# PennyMan_Ard_R3_Shield_v9_4.net
KiCad netlist of a schematic drawn in EAGLE
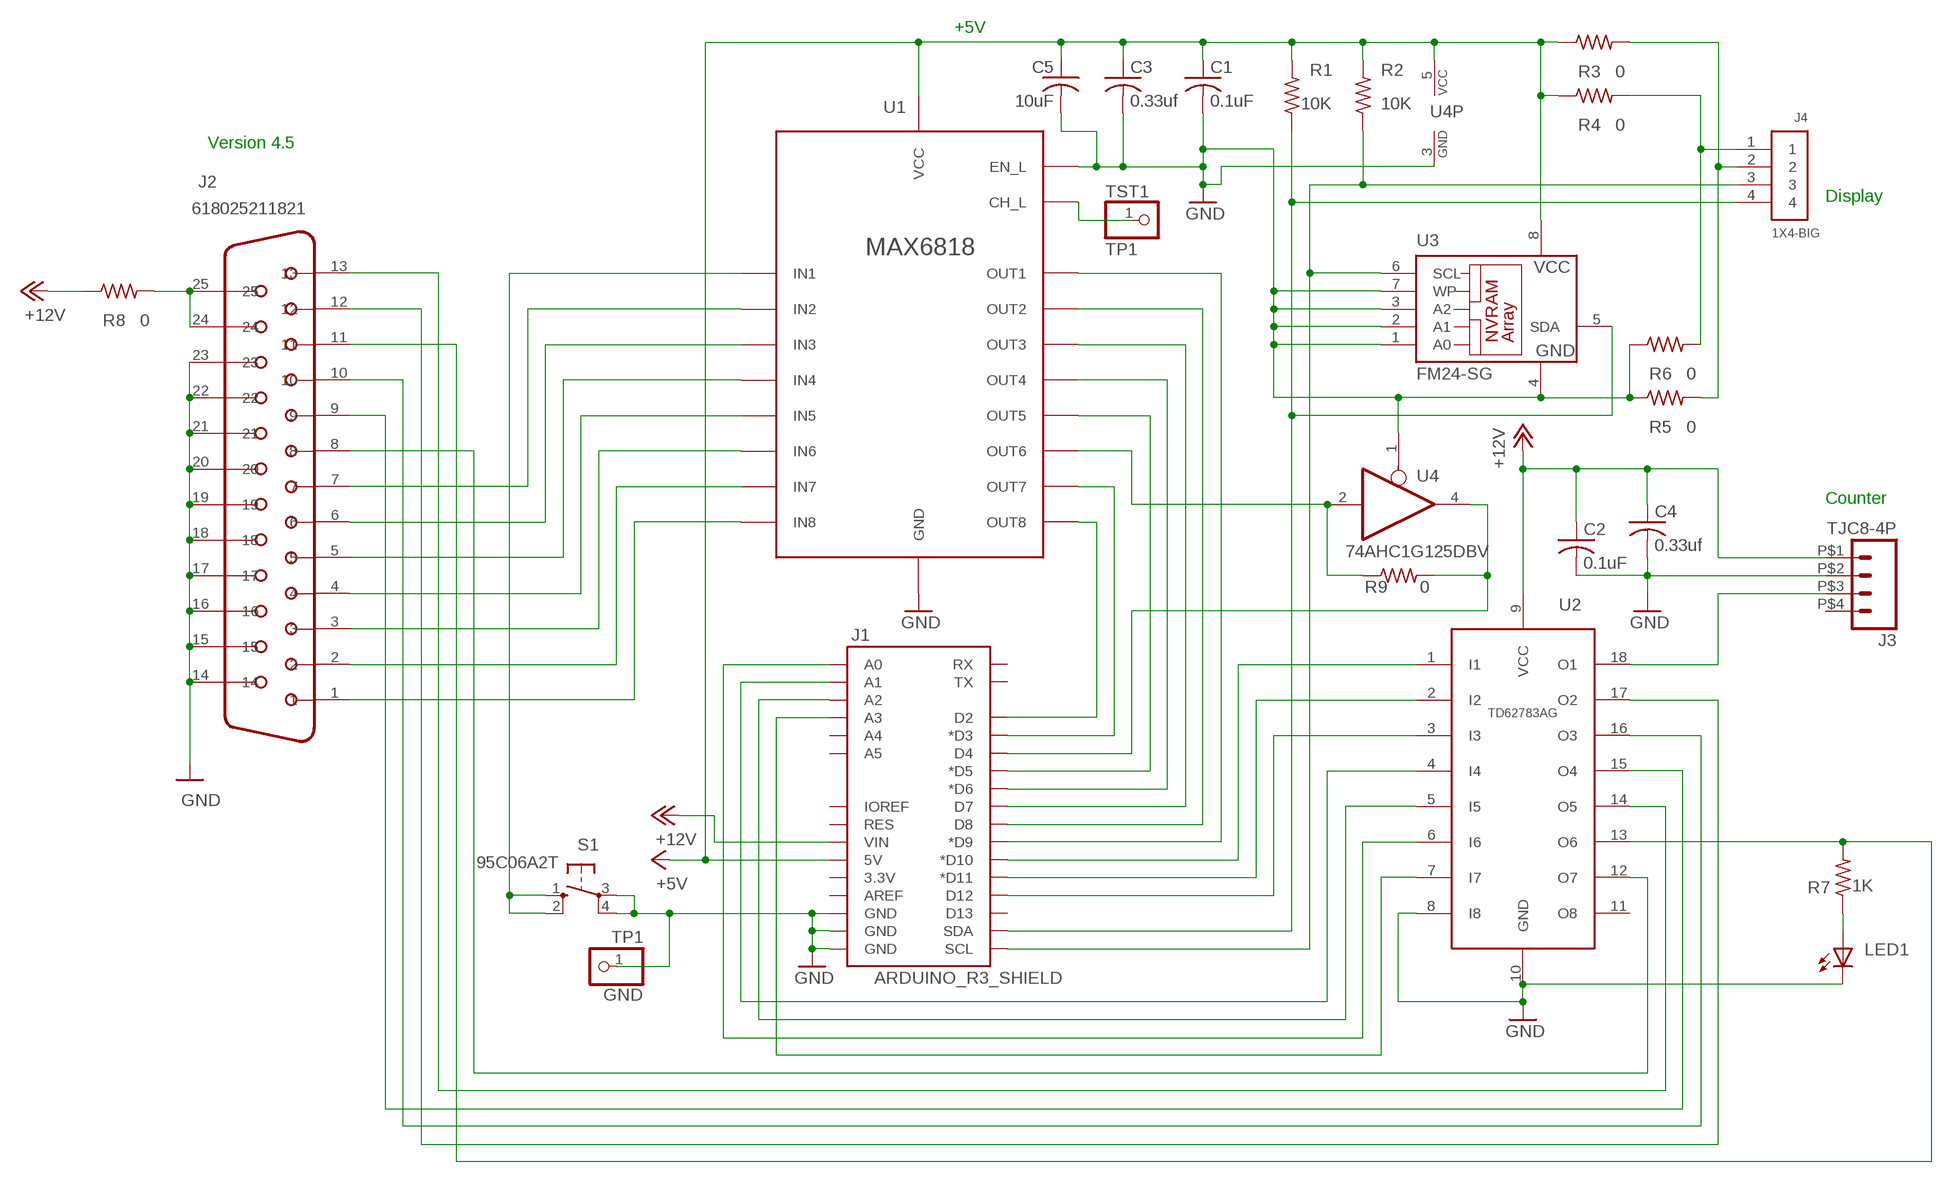
[diagram p0: schematic, sheet 1]

(export (version "E")
  (design (tool "Eeschema 10.0.6"))
  (components
    (comp (ref "C1")
      (value "0.1uF")
      (footprint "eagle-import:C0805")
      (libsource (lib "eagle-import") (part "C-USC0805"))
    )
    (comp (ref "C2")
      (value "0.1uF")
      (footprint "eagle-import:C0805")
      (libsource (lib "eagle-import") (part "C-USC0805"))
    )
    (comp (ref "C3")
      (value "0.33uf")
      (footprint "eagle-import:C1206")
      (libsource (lib "eagle-import") (part "C-USC1206"))
    )
    (comp (ref "C4")
      (value "0.33uf")
      (footprint "eagle-import:C1206")
      (libsource (lib "eagle-import") (part "C-USC1206"))
    )
    (comp (ref "C5")
      (value "10uF")
      (footprint "eagle-import:C1812")
      (libsource (lib "eagle-import") (part "C-USC1812"))
    )
    (comp (ref "GND")
      (value "TP1")
      (footprint "eagle-import:1X01")
      (libsource (lib "eagle-import") (part "PINHD-1X1"))
    )
    (comp (ref "J1")
      (value "ARDUINO_R3_SHIELD")
      (footprint "eagle-import:UNO_R3_SHIELD")
      (libsource (lib "eagle-import") (part "ARDUINO_R3_SHIELD"))
    )
    (comp (ref "J2")
      (value "618025211821")
      (footprint "eagle-import:618025211821")
      (libsource (lib "eagle-import") (part "618025211821"))
    )
    (comp (ref "J3")
      (value "TJC8-4P")
      (footprint "eagle-import:TJC8-4P")
      (libsource (lib "eagle-import") (part "TJC8-4P"))
    )
    (comp (ref "J4")
      (value "1X4-BIG")
      (footprint "eagle-import:1X04-BIG")
      (libsource (lib "eagle-import") (part "1X4-BIG"))
    )
    (comp (ref "LED1")
      (value "LEDSML0805")
      (footprint "eagle-import:SML0805")
      (libsource (lib "eagle-import") (part "LEDSML0805"))
    )
    (comp (ref "R1")
      (value "10K")
      (footprint "eagle-import:R0805")
      (libsource (lib "eagle-import") (part "R-US_R0805"))
    )
    (comp (ref "R2")
      (value "10K")
      (footprint "eagle-import:R0805")
      (libsource (lib "eagle-import") (part "R-US_R0805"))
    )
    (comp (ref "R3")
      (value "0")
      (footprint "eagle-import:R0805")
      (libsource (lib "eagle-import") (part "R-US_R0805"))
    )
    (comp (ref "R4")
      (value "0")
      (footprint "eagle-import:R0805")
      (libsource (lib "eagle-import") (part "R-US_R0805"))
    )
    (comp (ref "R5")
      (value "0")
      (footprint "eagle-import:R0805")
      (libsource (lib "eagle-import") (part "R-US_R0805"))
    )
    (comp (ref "R6")
      (value "0")
      (footprint "eagle-import:R0805")
      (libsource (lib "eagle-import") (part "R-US_R0805"))
    )
    (comp (ref "R7")
      (value "1K")
      (footprint "eagle-import:R0805")
      (libsource (lib "eagle-import") (part "R-US_R0805"))
    )
    (comp (ref "R8")
      (value "0")
      (footprint "eagle-import:R0805")
      (libsource (lib "eagle-import") (part "R-US_R0805"))
    )
    (comp (ref "R9")
      (value "0")
      (footprint "eagle-import:R0805")
      (libsource (lib "eagle-import") (part "R-US_R0805"))
    )
    (comp (ref "S1")
      (value "95C06A2T")
      (footprint "eagle-import:B3F-10XX")
      (libsource (lib "eagle-import") (part "10-XX"))
    )
    (comp (ref "TST1")
      (value "TP1")
      (footprint "eagle-import:1X01")
      (libsource (lib "eagle-import") (part "PINHD-1X1"))
    )
    (comp (ref "U1")
      (value "MAX6818")
      (footprint "eagle-import:SSOP20")
      (libsource (lib "eagle-import") (part "MAX6818"))
    )
    (comp (ref "U2")
      (value "TD62783AG")
      (footprint "eagle-import:SOP18")
      (libsource (lib "eagle-import") (part "TD62783AG"))
    )
    (comp (ref "U3")
      (value "FM24-SG")
      (footprint "eagle-import:SO8")
      (libsource (lib "eagle-import") (part "FM24-SG"))
    )
    (comp (ref "U4")
      (value "74AHC1G125DBV")
      (footprint "eagle-import:SOT23-5")
      (libsource (lib "eagle-import") (part "741G125DBVAHC"))
    )
  )
  (nets
    (net (code "1") (name "+5V") (class "Default")
      (node (ref "C1") (pin "1") (pinfunction "1_1") (pintype "passive"))
      (node (ref "C3") (pin "1") (pinfunction "1_1") (pintype "passive"))
      (node (ref "C5") (pin "1") (pinfunction "1_1") (pintype "passive"))
      (node (ref "J1") (pin "5V") (pinfunction "5V_5V") (pintype "bidirectional"))
      (node (ref "R1") (pin "2") (pinfunction "2_2") (pintype "passive"))
      (node (ref "R2") (pin "2") (pinfunction "2_2") (pintype "passive"))
      (node (ref "R3") (pin "1") (pinfunction "1_1") (pintype "passive"))
      (node (ref "R4") (pin "1") (pinfunction "1_1") (pintype "passive"))
      (node (ref "U1") (pin "VCC") (pinfunction "VCC_VCC") (pintype "bidirectional"))
      (node (ref "U3") (pin "8") (pinfunction "VCC_8") (pintype "power_in"))
      (node (ref "U4") (pin "5") (pinfunction "VCC_5") (pintype "power_in"))
    )
    (net (code "2") (name "+12V") (class "Default")
      (node (ref "C2") (pin "1") (pinfunction "1_1") (pintype "passive"))
      (node (ref "C4") (pin "1") (pinfunction "1_1") (pintype "passive"))
      (node (ref "J1") (pin "VIN") (pinfunction "VIN_VIN") (pintype "bidirectional"))
      (node (ref "J3") (pin "P$1") (pinfunction "1_P$1") (pintype "passive"))
      (node (ref "R8") (pin "1") (pinfunction "1_1") (pintype "passive"))
      (node (ref "U2") (pin "9") (pinfunction "VCC_9") (pintype "bidirectional"))
    )
    (net (code "3") (name "GND") (class "Default")
      (node (ref "C1") (pin "2") (pinfunction "2_2") (pintype "passive"))
      (node (ref "C2") (pin "2") (pinfunction "2_2") (pintype "passive"))
      (node (ref "C3") (pin "2") (pinfunction "2_2") (pintype "passive"))
      (node (ref "C4") (pin "2") (pinfunction "2_2") (pintype "passive"))
      (node (ref "C5") (pin "2") (pinfunction "2_2") (pintype "passive"))
      (node (ref "GND") (pin "1") (pinfunction "1_1") (pintype "passive"))
      (node (ref "J1") (pin "GND@0") (pinfunction "GND_GND@0") (pintype "bidirectional"))
      (node (ref "J1") (pin "GND@1") (pinfunction "GND_GND@1") (pintype "bidirectional"))
      (node (ref "J1") (pin "GND@2") (pinfunction "GND_GND@2") (pintype "bidirectional"))
      (node (ref "J2") (pin "14") (pinfunction "14_14") (pintype "bidirectional"))
      (node (ref "J2") (pin "15") (pinfunction "15_15") (pintype "bidirectional"))
      (node (ref "J2") (pin "16") (pinfunction "16_16") (pintype "bidirectional"))
      (node (ref "J2") (pin "17") (pinfunction "17_17") (pintype "bidirectional"))
      (node (ref "J2") (pin "18") (pinfunction "18_18") (pintype "bidirectional"))
      (node (ref "J2") (pin "19") (pinfunction "19_19") (pintype "bidirectional"))
      (node (ref "J2") (pin "20") (pinfunction "20_20") (pintype "bidirectional"))
      (node (ref "J2") (pin "21") (pinfunction "21_21") (pintype "bidirectional"))
      (node (ref "J2") (pin "22") (pinfunction "22_22") (pintype "bidirectional"))
      (node (ref "J2") (pin "23") (pinfunction "23_23") (pintype "bidirectional"))
      (node (ref "J3") (pin "P$2") (pinfunction "2_P$2") (pintype "passive"))
      (node (ref "LED1") (pin "C") (pinfunction "C_C") (pintype "passive"))
      (node (ref "R5") (pin "1") (pinfunction "1_1") (pintype "passive"))
      (node (ref "R6") (pin "1") (pinfunction "1_1") (pintype "passive"))
      (node (ref "S1") (pin "3") (pinfunction "P_3") (pintype "passive"))
      (node (ref "S1") (pin "4") (pinfunction "P1_4") (pintype "passive"))
      (node (ref "U1") (pin "EN_L") (pinfunction "EN_L_EN_L") (pintype "bidirectional"))
      (node (ref "U1") (pin "GND") (pinfunction "GND_GND") (pintype "bidirectional"))
      (node (ref "U2") (pin "10") (pinfunction "GND_10") (pintype "bidirectional"))
      (node (ref "U2") (pin "8") (pinfunction "I8_8") (pintype "bidirectional"))
      (node (ref "U3") (pin "1") (pinfunction "A0_1") (pintype "passive"))
      (node (ref "U3") (pin "2") (pinfunction "A1_2") (pintype "passive"))
      (node (ref "U3") (pin "3") (pinfunction "A2_3") (pintype "passive"))
      (node (ref "U3") (pin "4") (pinfunction "GND_4") (pintype "power_in"))
      (node (ref "U3") (pin "7") (pinfunction "WP_7") (pintype "input"))
      (node (ref "U4") (pin "1") (pinfunction "OE_1") (pintype "input"))
      (node (ref "U4") (pin "3") (pinfunction "GND_3") (pintype "power_in"))
    )
    (net (code "4") (name "Net-(J1-*D3)") (class "Default")
      (node (ref "J1") (pin "D3") (pinfunction "*D3_D3") (pintype "bidirectional"))
      (node (ref "U1") (pin "OUT7") (pinfunction "OUT7_OUT7") (pintype "bidirectional"))
    )
    (net (code "5") (name "Net-(J1-*D5)") (class "Default")
      (node (ref "J1") (pin "D5") (pinfunction "*D5_D5") (pintype "bidirectional"))
      (node (ref "U1") (pin "OUT5") (pinfunction "OUT5_OUT5") (pintype "bidirectional"))
    )
    (net (code "6") (name "Net-(J1-*D6)") (class "Default")
      (node (ref "J1") (pin "D6") (pinfunction "*D6_D6") (pintype "bidirectional"))
      (node (ref "U1") (pin "OUT4") (pinfunction "OUT4_OUT4") (pintype "bidirectional"))
    )
    (net (code "7") (name "Net-(J1-*D9)") (class "Default")
      (node (ref "J1") (pin "D9") (pinfunction "*D9_D9") (pintype "bidirectional"))
      (node (ref "U1") (pin "OUT1") (pinfunction "OUT1_OUT1") (pintype "bidirectional"))
    )
    (net (code "8") (name "Net-(J1-*D10)") (class "Default")
      (node (ref "J1") (pin "D10") (pinfunction "*D10_D10") (pintype "bidirectional"))
      (node (ref "U2") (pin "1") (pinfunction "I1_1") (pintype "bidirectional"))
    )
    (net (code "9") (name "Net-(J1-*D11)") (class "Default")
      (node (ref "J1") (pin "D11") (pinfunction "*D11_D11") (pintype "bidirectional"))
      (node (ref "U2") (pin "2") (pinfunction "I2_2") (pintype "bidirectional"))
    )
    (net (code "10") (name "Net-(J1-PadD2)") (class "Default")
      (node (ref "J1") (pin "D2") (pinfunction "D2_D2") (pintype "bidirectional"))
      (node (ref "U1") (pin "OUT8") (pinfunction "OUT8_OUT8") (pintype "bidirectional"))
    )
    (net (code "11") (name "Net-(J1-PadD7)") (class "Default")
      (node (ref "J1") (pin "D7") (pinfunction "D7_D7") (pintype "bidirectional"))
      (node (ref "U1") (pin "OUT3") (pinfunction "OUT3_OUT3") (pintype "bidirectional"))
    )
    (net (code "12") (name "Net-(J1-PadD8)") (class "Default")
      (node (ref "J1") (pin "D8") (pinfunction "D8_D8") (pintype "bidirectional"))
      (node (ref "U1") (pin "OUT2") (pinfunction "OUT2_OUT2") (pintype "bidirectional"))
    )
    (net (code "13") (name "Net-(J2-Pad1)") (class "Default")
      (node (ref "J2") (pin "1") (pinfunction "1_1") (pintype "bidirectional"))
      (node (ref "U1") (pin "IN8") (pinfunction "IN8_IN8") (pintype "bidirectional"))
    )
    (net (code "14") (name "Net-(J2-Pad2)") (class "Default")
      (node (ref "J2") (pin "2") (pinfunction "2_2") (pintype "bidirectional"))
      (node (ref "U1") (pin "IN7") (pinfunction "IN7_IN7") (pintype "bidirectional"))
    )
    (net (code "15") (name "Net-(J2-Pad3)") (class "Default")
      (node (ref "J2") (pin "3") (pinfunction "3_3") (pintype "bidirectional"))
      (node (ref "U1") (pin "IN6") (pinfunction "IN6_IN6") (pintype "bidirectional"))
    )
    (net (code "16") (name "Net-(J2-Pad4)") (class "Default")
      (node (ref "J2") (pin "4") (pinfunction "4_4") (pintype "bidirectional"))
      (node (ref "U1") (pin "IN5") (pinfunction "IN5_IN5") (pintype "bidirectional"))
    )
    (net (code "17") (name "Net-(J2-Pad5)") (class "Default")
      (node (ref "J2") (pin "5") (pinfunction "5_5") (pintype "bidirectional"))
      (node (ref "U1") (pin "IN4") (pinfunction "IN4_IN4") (pintype "bidirectional"))
    )
    (net (code "18") (name "Net-(J2-Pad6)") (class "Default")
      (node (ref "J2") (pin "6") (pinfunction "6_6") (pintype "bidirectional"))
      (node (ref "U1") (pin "IN3") (pinfunction "IN3_IN3") (pintype "bidirectional"))
    )
    (net (code "19") (name "Net-(J2-Pad7)") (class "Default")
      (node (ref "J2") (pin "7") (pinfunction "7_7") (pintype "bidirectional"))
      (node (ref "U1") (pin "IN2") (pinfunction "IN2_IN2") (pintype "bidirectional"))
    )
    (net (code "20") (name "Net-(J2-Pad24)") (class "Default")
      (node (ref "J2") (pin "24") (pinfunction "24_24") (pintype "bidirectional"))
      (node (ref "J2") (pin "25") (pinfunction "25_25") (pintype "bidirectional"))
      (node (ref "R8") (pin "2") (pinfunction "2_2") (pintype "passive"))
    )
    (net (code "21") (name "Net-(J3-3)") (class "Default")
      (node (ref "J3") (pin "P$3") (pinfunction "3_P$3") (pintype "passive"))
      (node (ref "U2") (pin "18") (pinfunction "O1_18") (pintype "bidirectional"))
    )
    (net (code "22") (name "Net-(J4-Pad1)") (class "Default")
      (node (ref "J4") (pin "1") (pinfunction "1_1") (pintype "bidirectional"))
      (node (ref "R4") (pin "2") (pinfunction "2_2") (pintype "passive"))
      (node (ref "R6") (pin "2") (pinfunction "2_2") (pintype "passive"))
    )
    (net (code "23") (name "Net-(J4-Pad2)") (class "Default")
      (node (ref "J4") (pin "2") (pinfunction "2_2") (pintype "bidirectional"))
      (node (ref "R3") (pin "2") (pinfunction "2_2") (pintype "passive"))
      (node (ref "R5") (pin "2") (pinfunction "2_2") (pintype "passive"))
    )
    (net (code "24") (name "Net-(LED1-PadA)") (class "Default")
      (node (ref "LED1") (pin "A") (pinfunction "A_A") (pintype "passive"))
      (node (ref "R7") (pin "1") (pinfunction "1_1") (pintype "passive"))
    )
    (net (code "25") (name "Net-(S1-S)") (class "Default")
      (node (ref "S1") (pin "1") (pinfunction "S_1") (pintype "passive"))
      (node (ref "S1") (pin "2") (pinfunction "S1_2") (pintype "passive"))
      (node (ref "U1") (pin "IN1") (pinfunction "IN1_IN1") (pintype "bidirectional"))
    )
    (net (code "26") (name "Net-(TST1-Pad1)") (class "Default")
      (node (ref "TST1") (pin "1") (pinfunction "1_1") (pintype "passive"))
      (node (ref "U1") (pin "CH_L") (pinfunction "CH_L_CH_L") (pintype "bidirectional"))
    )
    (net (code "27") (name "Net-(U2-I3)") (class "Default")
      (node (ref "J1") (pin "D12") (pinfunction "D12_D12") (pintype "bidirectional"))
      (node (ref "U2") (pin "3") (pinfunction "I3_3") (pintype "bidirectional"))
    )
    (net (code "28") (name "Net-(U2-I4)") (class "Default")
      (node (ref "J1") (pin "A1") (pinfunction "A1_A1") (pintype "bidirectional"))
      (node (ref "U2") (pin "4") (pinfunction "I4_4") (pintype "bidirectional"))
    )
    (net (code "29") (name "Net-(U2-I5)") (class "Default")
      (node (ref "J1") (pin "A2") (pinfunction "A2_A2") (pintype "bidirectional"))
      (node (ref "U2") (pin "5") (pinfunction "I5_5") (pintype "bidirectional"))
    )
    (net (code "30") (name "Net-(U2-I6)") (class "Default")
      (node (ref "J1") (pin "A0") (pinfunction "A0_A0") (pintype "bidirectional"))
      (node (ref "U2") (pin "6") (pinfunction "I6_6") (pintype "bidirectional"))
    )
    (net (code "31") (name "Net-(U2-I7)") (class "Default")
      (node (ref "J1") (pin "A3") (pinfunction "A3_A3") (pintype "bidirectional"))
      (node (ref "U2") (pin "7") (pinfunction "I7_7") (pintype "bidirectional"))
    )
    (net (code "32") (name "Net-(U2-O2)") (class "Default")
      (node (ref "J2") (pin "12") (pinfunction "12_12") (pintype "bidirectional"))
      (node (ref "U2") (pin "17") (pinfunction "O2_17") (pintype "bidirectional"))
    )
    (net (code "33") (name "Net-(U2-O3)") (class "Default")
      (node (ref "J2") (pin "10") (pinfunction "10_10") (pintype "bidirectional"))
      (node (ref "U2") (pin "16") (pinfunction "O3_16") (pintype "bidirectional"))
    )
    (net (code "34") (name "Net-(U2-O4)") (class "Default")
      (node (ref "J2") (pin "9") (pinfunction "9_9") (pintype "bidirectional"))
      (node (ref "U2") (pin "15") (pinfunction "O4_15") (pintype "bidirectional"))
    )
    (net (code "35") (name "Net-(U2-O5)") (class "Default")
      (node (ref "J2") (pin "13") (pinfunction "13_13") (pintype "bidirectional"))
      (node (ref "U2") (pin "14") (pinfunction "O5_14") (pintype "bidirectional"))
    )
    (net (code "36") (name "Net-(U2-O6)") (class "Default")
      (node (ref "J2") (pin "11") (pinfunction "11_11") (pintype "bidirectional"))
      (node (ref "R7") (pin "2") (pinfunction "2_2") (pintype "passive"))
      (node (ref "U2") (pin "13") (pinfunction "O6_13") (pintype "bidirectional"))
    )
    (net (code "37") (name "Net-(U2-O7)") (class "Default")
      (node (ref "J2") (pin "8") (pinfunction "8_8") (pintype "bidirectional"))
      (node (ref "U2") (pin "12") (pinfunction "O7_12") (pintype "bidirectional"))
    )
    (net (code "38") (name "Net-(U3-SCL)") (class "Default")
      (node (ref "J1") (pin "SCL") (pinfunction "SCL_SCL") (pintype "bidirectional"))
      (node (ref "J4") (pin "3") (pinfunction "3_3") (pintype "bidirectional"))
      (node (ref "R2") (pin "1") (pinfunction "1_1") (pintype "passive"))
      (node (ref "U3") (pin "6") (pinfunction "SCL_6") (pintype "input"))
    )
    (net (code "39") (name "Net-(U3-SDA)") (class "Default")
      (node (ref "J1") (pin "SDA") (pinfunction "SDA_SDA") (pintype "bidirectional"))
      (node (ref "J4") (pin "4") (pinfunction "4_4") (pintype "bidirectional"))
      (node (ref "R1") (pin "1") (pinfunction "1_1") (pintype "passive"))
      (node (ref "U3") (pin "5") (pinfunction "SDA_5") (pintype "bidirectional"))
    )
    (net (code "40") (name "Net-(U4A-I)") (class "Default")
      (node (ref "R9") (pin "1") (pinfunction "1_1") (pintype "passive"))
      (node (ref "U1") (pin "OUT6") (pinfunction "OUT6_OUT6") (pintype "bidirectional"))
      (node (ref "U4") (pin "2") (pinfunction "I_2") (pintype "input"))
    )
    (net (code "41") (name "Net-(U4A-O)") (class "Default")
      (node (ref "J1") (pin "D4") (pinfunction "D4_D4") (pintype "bidirectional"))
      (node (ref "R9") (pin "2") (pinfunction "2_2") (pintype "passive"))
      (node (ref "U4") (pin "4") (pinfunction "O_4") (pintype "tri_state"))
    )
    (net (code "42") (name "unconnected-(J1-Pad3.3V)") (class "Default")
      (node (ref "J1") (pin "3.3V") (pinfunction "3.3V_3.3V") (pintype "bidirectional"))
    )
    (net (code "43") (name "unconnected-(J1-PadA4)") (class "Default")
      (node (ref "J1") (pin "A4") (pinfunction "A4_A4") (pintype "bidirectional"))
    )
    (net (code "44") (name "unconnected-(J1-PadA5)") (class "Default")
      (node (ref "J1") (pin "A5") (pinfunction "A5_A5") (pintype "bidirectional"))
    )
    (net (code "45") (name "unconnected-(J1-PadAREF)") (class "Default")
      (node (ref "J1") (pin "AREF") (pinfunction "AREF_AREF") (pintype "bidirectional"))
    )
    (net (code "46") (name "unconnected-(J1-PadD13)") (class "Default")
      (node (ref "J1") (pin "D13") (pinfunction "D13_D13") (pintype "bidirectional"))
    )
    (net (code "47") (name "unconnected-(J1-PadIOREF)") (class "Default")
      (node (ref "J1") (pin "IOREF") (pinfunction "IOREF_IOREF") (pintype "bidirectional"))
    )
    (net (code "48") (name "unconnected-(J1-PadRES)") (class "Default")
      (node (ref "J1") (pin "RES") (pinfunction "RES_RES") (pintype "bidirectional"))
    )
    (net (code "49") (name "unconnected-(J1-PadRX)") (class "Default")
      (node (ref "J1") (pin "RX") (pinfunction "RX_RX") (pintype "bidirectional"))
    )
    (net (code "50") (name "unconnected-(J1-PadTX)") (class "Default")
      (node (ref "J1") (pin "TX") (pinfunction "TX_TX") (pintype "bidirectional"))
    )
    (net (code "51") (name "unconnected-(J3-4-PadP$4)") (class "Default")
      (node (ref "J3") (pin "P$4") (pinfunction "4_P$4") (pintype "passive"))
    )
    (net (code "52") (name "unconnected-(U2-O8-Pad11)") (class "Default")
      (node (ref "U2") (pin "11") (pinfunction "O8_11") (pintype "bidirectional"))
    )
  )
)
